# APUC.net
KiCad netlist of a schematic drawn in EAGLE
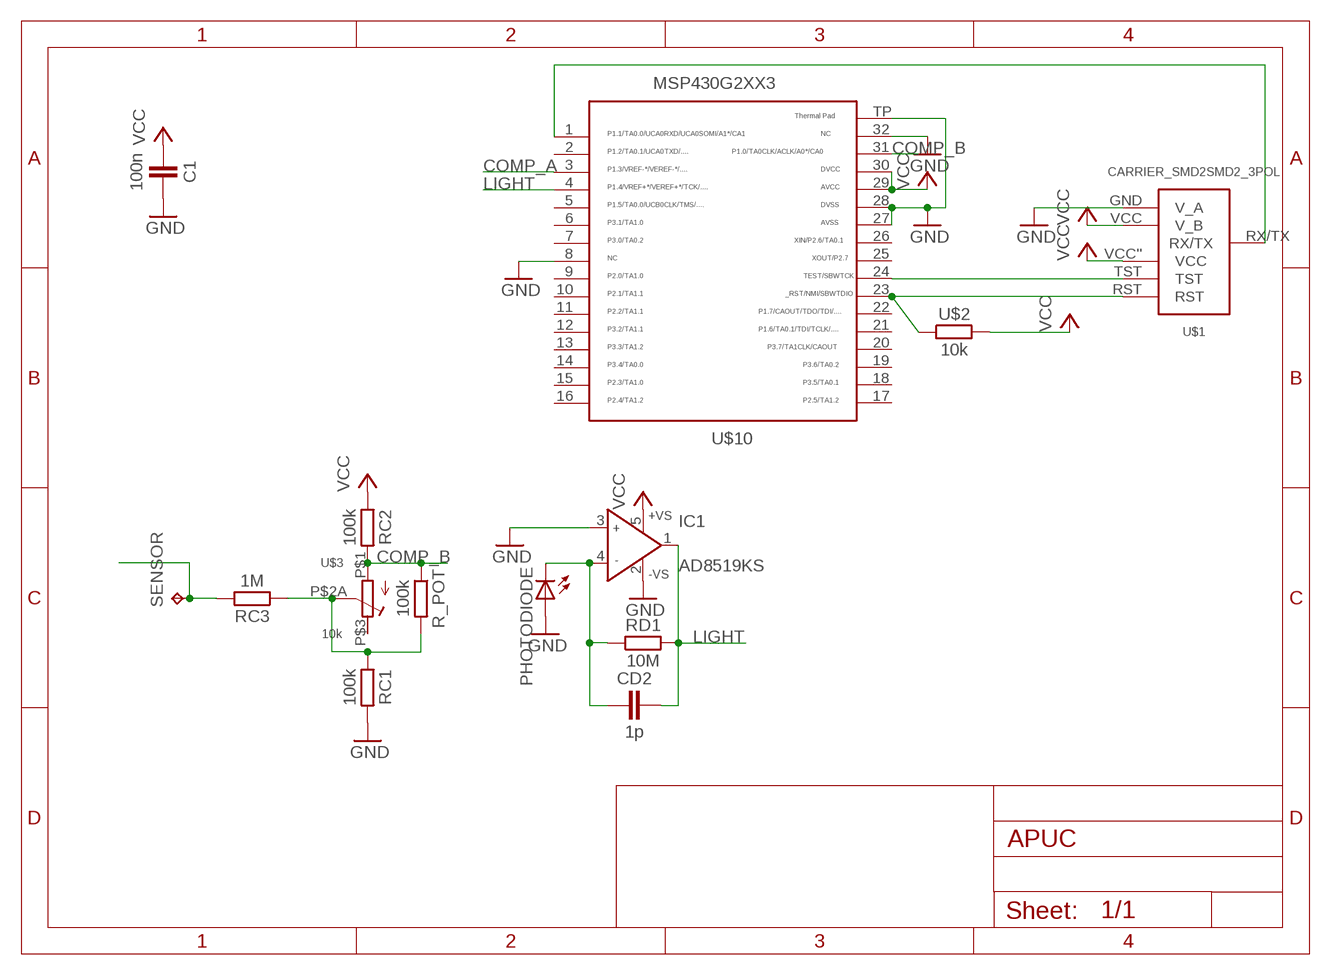
[diagram p0: schematic, sheet 1]

(export (version "E")
  (design (tool "Eeschema 10.0.6"))
  (components
    (comp (ref "C1")
      (value "100n")
      (footprint "eagle-import:603")
      (libsource (lib "eagle-import") (part "CAPACITOR"))
    )
    (comp (ref "CD2")
      (value "1p")
      (footprint "eagle-import:603")
      (libsource (lib "eagle-import") (part "CAPACITOR"))
    )
    (comp (ref "IC1")
      (value "AD8519KS")
      (footprint "eagle-import:SC70-5")
      (libsource (lib "eagle-import") (part "AD8519KS"))
    )
    (comp (ref "PHOTODIODE")
      (value "LEDCHIP-LED0805")
      (footprint "eagle-import:CHIP-LED0805")
      (libsource (lib "eagle-import") (part "LEDCHIP-LED0805"))
    )
    (comp (ref "RC1")
      (value "100k")
      (footprint "eagle-import:603")
      (libsource (lib "eagle-import") (part "RESISTOR0603"))
    )
    (comp (ref "RC2")
      (value "100k")
      (footprint "eagle-import:603")
      (libsource (lib "eagle-import") (part "RESISTOR0603"))
    )
    (comp (ref "RC3")
      (value "1M")
      (footprint "eagle-import:603")
      (libsource (lib "eagle-import") (part "RESISTOR0603"))
    )
    (comp (ref "RD1")
      (value "10M")
      (footprint "eagle-import:603")
      (libsource (lib "eagle-import") (part "RESISTOR0603"))
    )
    (comp (ref "R_POT")
      (value "100k")
      (footprint "eagle-import:603")
      (libsource (lib "eagle-import") (part "RESISTOR0603"))
    )
    (comp (ref "SENSOR")
      (value "TPTP20SQ")
      (footprint "eagle-import:TP20SQ")
      (libsource (lib "eagle-import") (part "TPTP20SQ"))
    )
    (comp (ref "U$1")
      (value "CARRIER_SMD2SMD2_3POL")
      (footprint "eagle-import:CARRIER_SMD2_3POL")
      (libsource (lib "eagle-import") (part "CARRIER_SMD2SMD2_3POL"))
    )
    (comp (ref "U$2")
      (value "10k")
      (footprint "eagle-import:603")
      (libsource (lib "eagle-import") (part "RESISTOR0603"))
    )
    (comp (ref "U$3")
      (value "10k")
      (footprint "eagle-import:MURATA-PVZ")
      (libsource (lib "eagle-import") (part "POTIMURATA_PVZ"))
    )
    (comp (ref "U$10")
      (value "MSP430G2553")
      (footprint "eagle-import:QFN32")
      (libsource (lib "eagle-import") (part "MSP430G2553"))
    )
  )
  (nets
    (net (code "1") (name "/COMP_A") (class "Default")
      (node (ref "RC3") (pin "2") (pinfunction "2_2") (pintype "passive"))
      (node (ref "SENSOR") (pin "TP") (pinfunction "TP_TP") (pintype "input"))
      (node (ref "U$10") (pin "3") (pinfunction "3_3") (pintype "bidirectional"))
    )
    (net (code "2") (name "/COMP_B") (class "Default")
      (node (ref "RC2") (pin "2") (pinfunction "2_2") (pintype "passive"))
      (node (ref "R_POT") (pin "1") (pinfunction "1_1") (pintype "passive"))
      (node (ref "U$10") (pin "31") (pinfunction "31_31") (pintype "bidirectional"))
      (node (ref "U$3") (pin "P$1") (pinfunction "A_P$1") (pintype "passive"))
    )
    (net (code "3") (name "/LIGHT") (class "Default")
      (node (ref "CD2") (pin "2") (pinfunction "2_2") (pintype "passive"))
      (node (ref "IC1") (pin "1") (pinfunction "OUT_1") (pintype "output"))
      (node (ref "RD1") (pin "2") (pinfunction "2_2") (pintype "passive"))
      (node (ref "U$10") (pin "4") (pinfunction "4_4") (pintype "bidirectional"))
    )
    (net (code "4") (name "GND") (class "Default")
      (node (ref "C1") (pin "2") (pinfunction "2_2") (pintype "passive"))
      (node (ref "IC1") (pin "2") (pinfunction "-VS_2") (pintype "input"))
      (node (ref "IC1") (pin "3") (pinfunction "IN+_3") (pintype "input"))
      (node (ref "PHOTODIODE") (pin "A") (pinfunction "A_A") (pintype "passive"))
      (node (ref "RC1") (pin "2") (pinfunction "2_2") (pintype "passive"))
      (node (ref "U$1") (pin "GND") (pinfunction "V_A_GND") (pintype "bidirectional"))
      (node (ref "U$10") (pin "27") (pinfunction "27_27") (pintype "bidirectional"))
      (node (ref "U$10") (pin "28") (pinfunction "28_28") (pintype "bidirectional"))
      (node (ref "U$10") (pin "32") (pinfunction "32_32") (pintype "bidirectional"))
      (node (ref "U$10") (pin "8") (pinfunction "8_8") (pintype "bidirectional"))
      (node (ref "U$10") (pin "TP") (pinfunction "TP_TP") (pintype "bidirectional"))
    )
    (net (code "5") (name "Net-(IC1-IN-)") (class "Default")
      (node (ref "CD2") (pin "1") (pinfunction "1_1") (pintype "passive"))
      (node (ref "IC1") (pin "4") (pinfunction "IN-_4") (pintype "input"))
      (node (ref "PHOTODIODE") (pin "C") (pinfunction "C_C") (pintype "passive"))
      (node (ref "RD1") (pin "1") (pinfunction "1_1") (pintype "passive"))
    )
    (net (code "6") (name "Net-(U$1-PadRST)") (class "Default")
      (node (ref "U$1") (pin "RST") (pinfunction "RST_RST") (pintype "bidirectional"))
      (node (ref "U$10") (pin "23") (pinfunction "23_23") (pintype "bidirectional"))
      (node (ref "U$2") (pin "1") (pinfunction "1_1") (pintype "passive"))
    )
    (net (code "7") (name "Net-(U$1-PadRX{slash}TX)") (class "Default")
      (node (ref "U$1") (pin "RX/TX") (pinfunction "RX/TX_RX/TX") (pintype "bidirectional"))
      (node (ref "U$10") (pin "1") (pinfunction "1_1") (pintype "bidirectional"))
    )
    (net (code "8") (name "Net-(U$1-PadTST)") (class "Default")
      (node (ref "U$1") (pin "TST") (pinfunction "TST_TST") (pintype "bidirectional"))
      (node (ref "U$10") (pin "24") (pinfunction "24_24") (pintype "bidirectional"))
    )
    (net (code "9") (name "Net-(U$3-S)") (class "Default")
      (node (ref "RC1") (pin "1") (pinfunction "1_1") (pintype "passive"))
      (node (ref "RC3") (pin "1") (pinfunction "1_1") (pintype "passive"))
      (node (ref "R_POT") (pin "2") (pinfunction "2_2") (pintype "passive"))
      (node (ref "U$3") (pin "P$2A") (pinfunction "S_P$2A") (pintype "passive"))
    )
    (net (code "10") (name "VCC") (class "Default")
      (node (ref "C1") (pin "1") (pinfunction "1_1") (pintype "passive"))
      (node (ref "IC1") (pin "5") (pinfunction "+VS_5") (pintype "input"))
      (node (ref "RC2") (pin "1") (pinfunction "1_1") (pintype "passive"))
      (node (ref "U$1") (pin "VCC") (pinfunction "V_B_VCC") (pintype "bidirectional"))
      (node (ref "U$1") (pin "VCC''") (pinfunction "VCC_VCC''") (pintype "bidirectional"))
      (node (ref "U$10") (pin "29") (pinfunction "29_29") (pintype "bidirectional"))
      (node (ref "U$10") (pin "30") (pinfunction "30_30") (pintype "bidirectional"))
      (node (ref "U$2") (pin "2") (pinfunction "2_2") (pintype "passive"))
    )
    (net (code "11") (name "unconnected-(U$3-E-PadP$3)") (class "Default")
      (node (ref "U$3") (pin "P$3") (pinfunction "E_P$3") (pintype "passive"))
    )
    (net (code "12") (name "unconnected-(U$10-Pad2)") (class "Default")
      (node (ref "U$10") (pin "2") (pinfunction "2_2") (pintype "bidirectional"))
    )
    (net (code "13") (name "unconnected-(U$10-Pad5)") (class "Default")
      (node (ref "U$10") (pin "5") (pinfunction "5_5") (pintype "bidirectional"))
    )
    (net (code "14") (name "unconnected-(U$10-Pad6)") (class "Default")
      (node (ref "U$10") (pin "6") (pinfunction "6_6") (pintype "bidirectional"))
    )
    (net (code "15") (name "unconnected-(U$10-Pad7)") (class "Default")
      (node (ref "U$10") (pin "7") (pinfunction "7_7") (pintype "bidirectional"))
    )
    (net (code "16") (name "unconnected-(U$10-Pad9)") (class "Default")
      (node (ref "U$10") (pin "9") (pinfunction "9_9") (pintype "bidirectional"))
    )
    (net (code "17") (name "unconnected-(U$10-Pad10)") (class "Default")
      (node (ref "U$10") (pin "10") (pinfunction "10_10") (pintype "bidirectional"))
    )
    (net (code "18") (name "unconnected-(U$10-Pad11)") (class "Default")
      (node (ref "U$10") (pin "11") (pinfunction "11_11") (pintype "bidirectional"))
    )
    (net (code "19") (name "unconnected-(U$10-Pad12)") (class "Default")
      (node (ref "U$10") (pin "12") (pinfunction "12_12") (pintype "bidirectional"))
    )
    (net (code "20") (name "unconnected-(U$10-Pad13)") (class "Default")
      (node (ref "U$10") (pin "13") (pinfunction "13_13") (pintype "bidirectional"))
    )
    (net (code "21") (name "unconnected-(U$10-Pad14)") (class "Default")
      (node (ref "U$10") (pin "14") (pinfunction "14_14") (pintype "bidirectional"))
    )
    (net (code "22") (name "unconnected-(U$10-Pad15)") (class "Default")
      (node (ref "U$10") (pin "15") (pinfunction "15_15") (pintype "bidirectional"))
    )
    (net (code "23") (name "unconnected-(U$10-Pad16)") (class "Default")
      (node (ref "U$10") (pin "16") (pinfunction "16_16") (pintype "bidirectional"))
    )
    (net (code "24") (name "unconnected-(U$10-Pad17)") (class "Default")
      (node (ref "U$10") (pin "17") (pinfunction "17_17") (pintype "bidirectional"))
    )
    (net (code "25") (name "unconnected-(U$10-Pad18)") (class "Default")
      (node (ref "U$10") (pin "18") (pinfunction "18_18") (pintype "bidirectional"))
    )
    (net (code "26") (name "unconnected-(U$10-Pad19)") (class "Default")
      (node (ref "U$10") (pin "19") (pinfunction "19_19") (pintype "bidirectional"))
    )
    (net (code "27") (name "unconnected-(U$10-Pad20)") (class "Default")
      (node (ref "U$10") (pin "20") (pinfunction "20_20") (pintype "bidirectional"))
    )
    (net (code "28") (name "unconnected-(U$10-Pad21)") (class "Default")
      (node (ref "U$10") (pin "21") (pinfunction "21_21") (pintype "bidirectional"))
    )
    (net (code "29") (name "unconnected-(U$10-Pad22)") (class "Default")
      (node (ref "U$10") (pin "22") (pinfunction "22_22") (pintype "bidirectional"))
    )
    (net (code "30") (name "unconnected-(U$10-Pad25)") (class "Default")
      (node (ref "U$10") (pin "25") (pinfunction "25_25") (pintype "bidirectional"))
    )
    (net (code "31") (name "unconnected-(U$10-Pad26)") (class "Default")
      (node (ref "U$10") (pin "26") (pinfunction "26_26") (pintype "bidirectional"))
    )
  )
)
